# buttons_audio_amplifier.net
KiCad netlist of a schematic drawn in Altium Designer
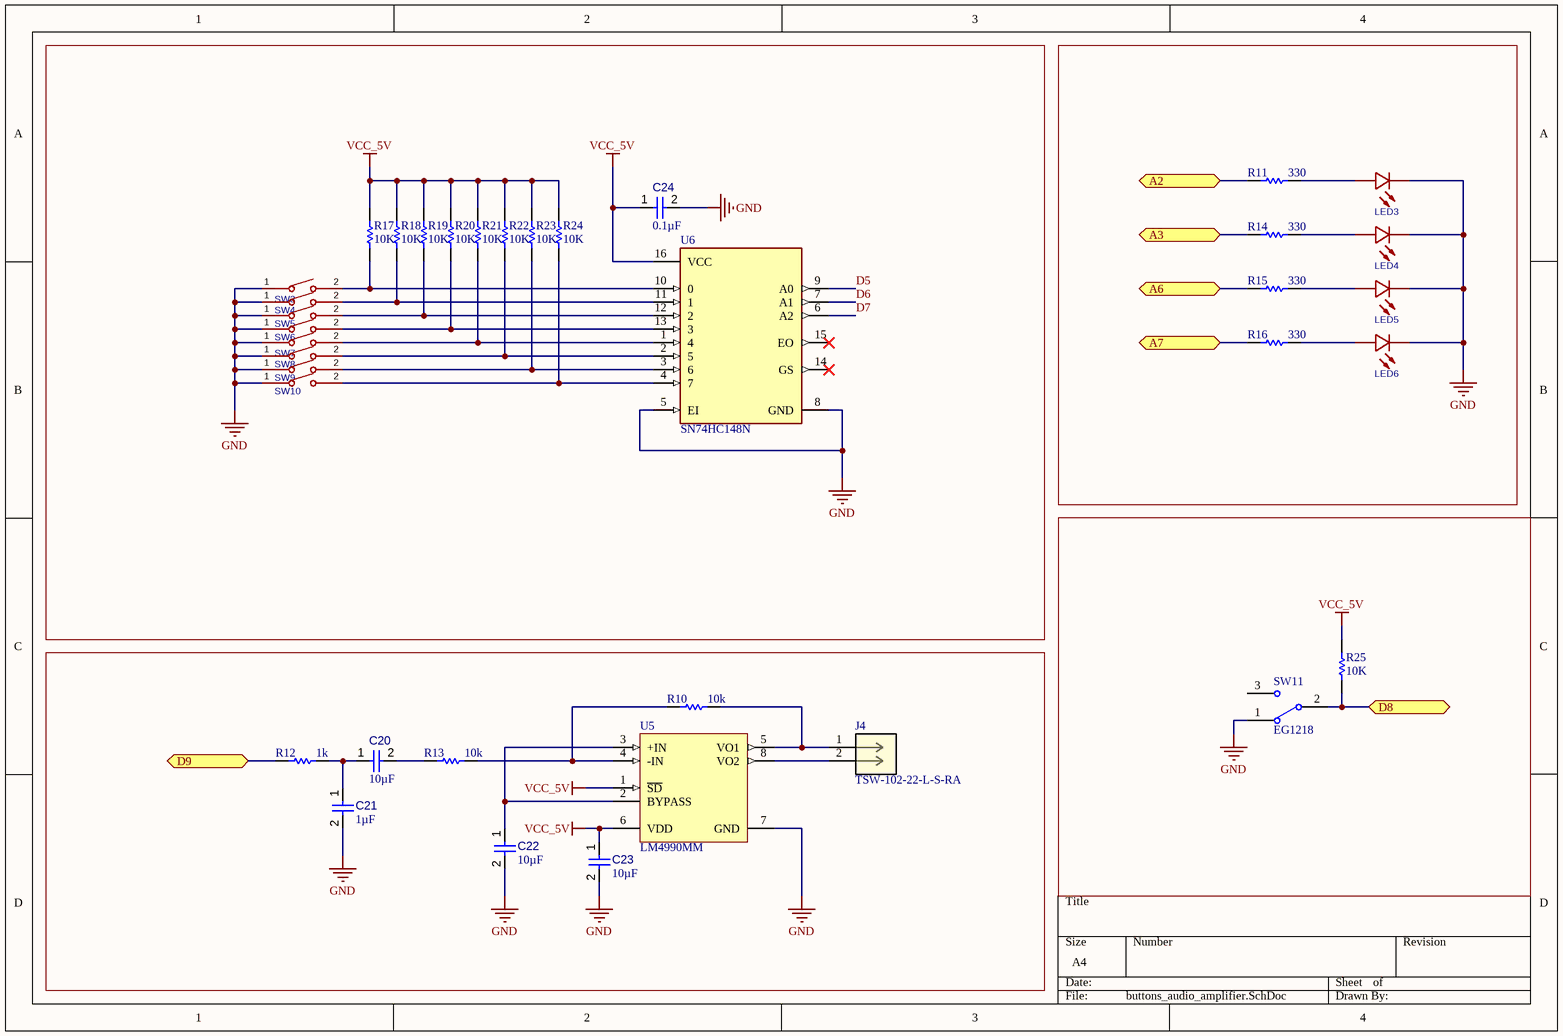
[diagram p0: buttons_audio_amplifier.SchDoc]

(export (version "E")
  (design (tool "Eeschema 10.0.6"))
  (components
    (comp (ref "C20")
      (value "10µF")
      (footprint "CAPC2013X135X45NL10T25")
      (description "Chip Capacitor, 10 uF, +/- 10%, 16 V, 0805 (2012 Metric)")
      (fields (field (name "TOLERANCE") "10%") (field (name "Comment") "Capacitor 10 uF +/- 10% 16 V 0805"))
      (libsource (lib "新宇 付") (part "CAP-NP-2"))
    )
    (comp (ref "C21")
      (value "1µF")
      (footprint "CAPC2013X135X45NL10T25")
      (description "Chip Capacitor, 10 uF, +/- 10%, 16 V, 0805 (2012 Metric)")
      (fields (field (name "TOLERANCE") "10%") (field (name "Comment") "Capacitor 10 uF +/- 10% 16 V 0805"))
      (libsource (lib "新宇 付") (part "CAP-NP-2"))
    )
    (comp (ref "C22")
      (value "10µF")
      (footprint "CAPC2013X135X45NL10T25")
      (description "Chip Capacitor, 10 uF, +/- 10%, 16 V, 0805 (2012 Metric)")
      (fields (field (name "TOLERANCE") "10%") (field (name "Comment") "Capacitor 10 uF +/- 10% 16 V 0805"))
      (libsource (lib "新宇 付") (part "CAP-NP-2"))
    )
    (comp (ref "C23")
      (value "10µF")
      (footprint "CAPC2013X135X45NL10T25")
      (description "Chip Capacitor, 10 uF, +/- 10%, 16 V, 0805 (2012 Metric)")
      (fields (field (name "TOLERANCE") "10%") (field (name "Comment") "Capacitor 10 uF +/- 10% 16 V 0805"))
      (libsource (lib "新宇 付") (part "CAP-NP-2"))
    )
    (comp (ref "C24")
      (value "0.1µF")
      (footprint "CAPC2013X135X45NL10T25")
      (description "Chip Capacitor, 10 uF, +/- 10%, 16 V, 0805 (2012 Metric)")
      (fields (field (name "TOLERANCE") "10%") (field (name "Comment") "Capacitor 10 uF +/- 10% 16 V 0805"))
      (libsource (lib "新宇 付") (part "CAP-NP-2"))
    )
    (comp (ref "J4")
      (value "TSW-102-22-L-S-RA")
      (footprint "CON2_1X2_TR_TSW_SAI")
      (description "No Description Available")
      (fields (field (name "COPYRIGHT") "Copyright (C) 2026 Ultra Librarian. All rights reserved."))
      (libsource (lib "TSW-102-22-L-S-RA") (part "TSW-102-22-L-S-RA"))
    )
    (comp (ref "LED3")
      (value "FC-DA1608HRK-620D")
      (footprint "LED0603-RD_RED")
      (libsource (lib "C84263_发光二极管-LED_0603") (part "FC-DA1608HRK-620D"))
    )
    (comp (ref "LED4")
      (value "FC-DA1608HRK-620D")
      (footprint "LED0603-RD_RED")
      (libsource (lib "C84263_发光二极管-LED_0603") (part "FC-DA1608HRK-620D"))
    )
    (comp (ref "LED5")
      (value "FC-DA1608HRK-620D")
      (footprint "LED0603-RD_RED")
      (libsource (lib "C84263_发光二极管-LED_0603") (part "FC-DA1608HRK-620D"))
    )
    (comp (ref "LED6")
      (value "FC-DA1608HRK-620D")
      (footprint "LED0603-RD_RED")
      (libsource (lib "C84263_发光二极管-LED_0603") (part "FC-DA1608HRK-620D"))
    )
    (comp (ref "R10")
      (value "10k")
      (footprint "RESC2013X50X35ML15T15")
      (description "Chip Resistor, 0 Ohm, +/- 1%, 125 mW, -55 to 155 degC, 0805 (2012 Metric)")
      (fields (field (name "TOLERANCE") "1%") (field (name "POWER") "125mW"))
      (libsource (lib "新宇 付") (part "RES-2"))
    )
    (comp (ref "R11")
      (value "330")
      (footprint "RESC2013X50X35ML15T15")
      (description "Chip Resistor, 0 Ohm, +/- 1%, 125 mW, -55 to 155 degC, 0805 (2012 Metric)")
      (fields (field (name "TOLERANCE") "1%") (field (name "POWER") "125mW"))
      (libsource (lib "新宇 付") (part "RES-2"))
    )
    (comp (ref "R12")
      (value "1k")
      (footprint "RESC2013X50X35ML15T15")
      (description "Chip Resistor, 0 Ohm, +/- 1%, 125 mW, -55 to 155 degC, 0805 (2012 Metric)")
      (fields (field (name "TOLERANCE") "1%") (field (name "POWER") "125mW"))
      (libsource (lib "新宇 付") (part "RES-2"))
    )
    (comp (ref "R13")
      (value "10k")
      (footprint "RESC2013X50X35ML15T15")
      (description "Chip Resistor, 0 Ohm, +/- 1%, 125 mW, -55 to 155 degC, 0805 (2012 Metric)")
      (fields (field (name "TOLERANCE") "1%") (field (name "POWER") "125mW"))
      (libsource (lib "新宇 付") (part "RES-2"))
    )
    (comp (ref "R14")
      (value "330")
      (footprint "RESC2013X50X35ML15T15")
      (description "Chip Resistor, 0 Ohm, +/- 1%, 125 mW, -55 to 155 degC, 0805 (2012 Metric)")
      (fields (field (name "TOLERANCE") "1%") (field (name "POWER") "125mW"))
      (libsource (lib "新宇 付") (part "RES-2"))
    )
    (comp (ref "R15")
      (value "330")
      (footprint "RESC2013X50X35ML15T15")
      (description "Chip Resistor, 0 Ohm, +/- 1%, 125 mW, -55 to 155 degC, 0805 (2012 Metric)")
      (fields (field (name "TOLERANCE") "1%") (field (name "POWER") "125mW"))
      (libsource (lib "新宇 付") (part "RES-2"))
    )
    (comp (ref "R16")
      (value "330")
      (footprint "RESC2013X50X35ML15T15")
      (description "Chip Resistor, 0 Ohm, +/- 1%, 125 mW, -55 to 155 degC, 0805 (2012 Metric)")
      (fields (field (name "TOLERANCE") "1%") (field (name "POWER") "125mW"))
      (libsource (lib "新宇 付") (part "RES-2"))
    )
    (comp (ref "R17")
      (value "10K")
      (footprint "RESC2013X50X35ML15T15")
      (description "Chip Resistor, 0 Ohm, +/- 1%, 125 mW, -55 to 155 degC, 0805 (2012 Metric)")
      (fields (field (name "TOLERANCE") "1%") (field (name "POWER") "125mW"))
      (libsource (lib "新宇 付") (part "RES-2"))
    )
    (comp (ref "R18")
      (value "10K")
      (footprint "RESC2013X50X35ML15T15")
      (description "Chip Resistor, 0 Ohm, +/- 1%, 125 mW, -55 to 155 degC, 0805 (2012 Metric)")
      (fields (field (name "TOLERANCE") "1%") (field (name "POWER") "125mW"))
      (libsource (lib "新宇 付") (part "RES-2"))
    )
    (comp (ref "R19")
      (value "10K")
      (footprint "RESC2013X50X35ML15T15")
      (description "Chip Resistor, 0 Ohm, +/- 1%, 125 mW, -55 to 155 degC, 0805 (2012 Metric)")
      (fields (field (name "TOLERANCE") "1%") (field (name "POWER") "125mW"))
      (libsource (lib "新宇 付") (part "RES-2"))
    )
    (comp (ref "R20")
      (value "10K")
      (footprint "RESC2013X50X35ML15T15")
      (description "Chip Resistor, 0 Ohm, +/- 1%, 125 mW, -55 to 155 degC, 0805 (2012 Metric)")
      (fields (field (name "TOLERANCE") "1%") (field (name "POWER") "125mW"))
      (libsource (lib "新宇 付") (part "RES-2"))
    )
    (comp (ref "R21")
      (value "10K")
      (footprint "RESC2013X50X35ML15T15")
      (description "Chip Resistor, 0 Ohm, +/- 1%, 125 mW, -55 to 155 degC, 0805 (2012 Metric)")
      (fields (field (name "TOLERANCE") "1%") (field (name "POWER") "125mW"))
      (libsource (lib "新宇 付") (part "RES-2"))
    )
    (comp (ref "R22")
      (value "10K")
      (footprint "RESC2013X50X35ML15T15")
      (description "Chip Resistor, 0 Ohm, +/- 1%, 125 mW, -55 to 155 degC, 0805 (2012 Metric)")
      (fields (field (name "TOLERANCE") "1%") (field (name "POWER") "125mW"))
      (libsource (lib "新宇 付") (part "RES-2"))
    )
    (comp (ref "R23")
      (value "10K")
      (footprint "RESC2013X50X35ML15T15")
      (description "Chip Resistor, 0 Ohm, +/- 1%, 125 mW, -55 to 155 degC, 0805 (2012 Metric)")
      (fields (field (name "TOLERANCE") "1%") (field (name "POWER") "125mW"))
      (libsource (lib "新宇 付") (part "RES-2"))
    )
    (comp (ref "R24")
      (value "10K")
      (footprint "RESC2013X50X35ML15T15")
      (description "Chip Resistor, 0 Ohm, +/- 1%, 125 mW, -55 to 155 degC, 0805 (2012 Metric)")
      (fields (field (name "TOLERANCE") "1%") (field (name "POWER") "125mW"))
      (libsource (lib "新宇 付") (part "RES-2"))
    )
    (comp (ref "R25")
      (value "10K")
      (footprint "RESC2013X50X35ML15T15")
      (description "Chip Resistor, 0 Ohm, +/- 1%, 125 mW, -55 to 155 degC, 0805 (2012 Metric)")
      (fields (field (name "TOLERANCE") "1%") (field (name "POWER") "125mW"))
      (libsource (lib "新宇 付") (part "RES-2"))
    )
    (comp (ref "SW3")
      (value "TS-1088-AR02016")
      (footprint "SW-SMD_L3.9-W3.0-P4.45")
      (libsource (lib "Click_switch") (part "TS-1088-AR02016"))
    )
    (comp (ref "SW4")
      (value "TS-1088-AR02016")
      (footprint "SW-SMD_L3.9-W3.0-P4.45")
      (libsource (lib "Click_switch") (part "TS-1088-AR02016"))
    )
    (comp (ref "SW5")
      (value "TS-1088-AR02016")
      (footprint "SW-SMD_L3.9-W3.0-P4.45")
      (libsource (lib "Click_switch") (part "TS-1088-AR02016"))
    )
    (comp (ref "SW6")
      (value "TS-1088-AR02016")
      (footprint "SW-SMD_L3.9-W3.0-P4.45")
      (libsource (lib "Click_switch") (part "TS-1088-AR02016"))
    )
    (comp (ref "SW7")
      (value "TS-1088-AR02016")
      (footprint "SW-SMD_L3.9-W3.0-P4.45")
      (libsource (lib "Click_switch") (part "TS-1088-AR02016"))
    )
    (comp (ref "SW8")
      (value "TS-1088-AR02016")
      (footprint "SW-SMD_L3.9-W3.0-P4.45")
      (libsource (lib "Click_switch") (part "TS-1088-AR02016"))
    )
    (comp (ref "SW9")
      (value "TS-1088-AR02016")
      (footprint "SW-SMD_L3.9-W3.0-P4.45")
      (libsource (lib "Click_switch") (part "TS-1088-AR02016"))
    )
    (comp (ref "SW10")
      (value "TS-1088-AR02016")
      (footprint "SW-SMD_L3.9-W3.0-P4.45")
      (libsource (lib "Click_switch") (part "TS-1088-AR02016"))
    )
    (comp (ref "SW11")
      (value "EG1218")
      (footprint "ESWI-EG1218_V")
      (description "Slide Switch, 500 V, -20 to 70 degC, 3-Pin THD, RoHS")
      (libsource (lib "EG1218单刀双掷滑动开关") (part "CMP-1696-00002-1"))
    )
    (comp (ref "U5")
      (value "LM4990MM")
      (footprint "DGK0008A_N")
      (description "2W Audio Power Amplifier with Selectable Shutdown Logic Level, 8-pin Mini SOIC")
      (fields (field (name "MANUFACTURER") "Texas Instruments"))
      (libsource (lib "Altium Content Vault") (part "AMP-APA-LM4876-8"))
    )
    (comp (ref "U6")
      (value "SN74HC148N")
      (footprint "FP-N0016A-MFG")
      (description "IC PRIORITY ENCOD 1 X 8:3 16DIP")
      (libsource (lib "Altium Content Vault") (part "d5208e0a127fb6c4f39bc57aee2ba58"))
    )
  )
  (nets
    (net (code "1") (name "/A2") (class "Default")
      (node (ref "R11") (pin "1") (pinfunction "1_1") (pintype "passive"))
    )
    (net (code "2") (name "/A3") (class "Default")
      (node (ref "R14") (pin "1") (pinfunction "1_1") (pintype "passive"))
    )
    (net (code "3") (name "/A6") (class "Default")
      (node (ref "R15") (pin "1") (pinfunction "1_1") (pintype "passive"))
    )
    (net (code "4") (name "/A7") (class "Default")
      (node (ref "R16") (pin "1") (pinfunction "1_1") (pintype "passive"))
    )
    (net (code "5") (name "/D5") (class "Default")
      (node (ref "U6") (pin "9") (pinfunction "A0_9") (pintype "output"))
    )
    (net (code "6") (name "/D6") (class "Default")
      (node (ref "U6") (pin "7") (pinfunction "A1_7") (pintype "output"))
    )
    (net (code "7") (name "/D7") (class "Default")
      (node (ref "U6") (pin "6") (pinfunction "A2_6") (pintype "output"))
    )
    (net (code "8") (name "/D8") (class "Default")
      (node (ref "R25") (pin "2") (pinfunction "2_2") (pintype "passive"))
      (node (ref "SW11") (pin "2") (pinfunction "COM_2") (pintype "passive"))
    )
    (net (code "9") (name "/D9") (class "Default")
      (node (ref "R12") (pin "1") (pinfunction "1_1") (pintype "passive"))
    )
    (net (code "10") (name "GND") (class "Default")
      (node (ref "C21") (pin "2") (pinfunction "2_2") (pintype "passive"))
      (node (ref "C22") (pin "2") (pinfunction "2_2") (pintype "passive"))
      (node (ref "C23") (pin "2") (pinfunction "2_2") (pintype "passive"))
      (node (ref "C24") (pin "2") (pinfunction "2_2") (pintype "passive"))
      (node (ref "LED3") (pin "1") (pinfunction "K_1") (pintype "passive"))
      (node (ref "LED4") (pin "1") (pinfunction "K_1") (pintype "passive"))
      (node (ref "LED5") (pin "1") (pinfunction "K_1") (pintype "passive"))
      (node (ref "LED6") (pin "1") (pinfunction "K_1") (pintype "passive"))
      (node (ref "SW10") (pin "1") (pinfunction "1_1") (pintype "passive"))
      (node (ref "SW11") (pin "1") (pinfunction "1_1") (pintype "passive"))
      (node (ref "SW3") (pin "1") (pinfunction "1_1") (pintype "passive"))
      (node (ref "SW4") (pin "1") (pinfunction "1_1") (pintype "passive"))
      (node (ref "SW5") (pin "1") (pinfunction "1_1") (pintype "passive"))
      (node (ref "SW6") (pin "1") (pinfunction "1_1") (pintype "passive"))
      (node (ref "SW7") (pin "1") (pinfunction "1_1") (pintype "passive"))
      (node (ref "SW8") (pin "1") (pinfunction "1_1") (pintype "passive"))
      (node (ref "SW9") (pin "1") (pinfunction "1_1") (pintype "passive"))
      (node (ref "U5") (pin "7") (pinfunction "GND_7") (pintype "power_in"))
      (node (ref "U6") (pin "5") (pinfunction "EI_5") (pintype "input"))
      (node (ref "U6") (pin "8") (pinfunction "GND_8") (pintype "power_in"))
    )
    (net (code "11") (name "Net-(C20-Pad1)") (class "Default")
      (node (ref "C20") (pin "1") (pinfunction "1_1") (pintype "passive"))
      (node (ref "C21") (pin "1") (pinfunction "1_1") (pintype "passive"))
      (node (ref "R12") (pin "2") (pinfunction "2_2") (pintype "passive"))
    )
    (net (code "12") (name "Net-(C20-Pad2)") (class "Default")
      (node (ref "C20") (pin "2") (pinfunction "2_2") (pintype "passive"))
      (node (ref "R13") (pin "1") (pinfunction "1_1") (pintype "passive"))
    )
    (net (code "13") (name "Net-(LED3-A)") (class "Default")
      (node (ref "LED3") (pin "2") (pinfunction "A_2") (pintype "passive"))
      (node (ref "R11") (pin "2") (pinfunction "2_2") (pintype "passive"))
    )
    (net (code "14") (name "Net-(LED4-A)") (class "Default")
      (node (ref "LED4") (pin "2") (pinfunction "A_2") (pintype "passive"))
      (node (ref "R14") (pin "2") (pinfunction "2_2") (pintype "passive"))
    )
    (net (code "15") (name "Net-(LED5-A)") (class "Default")
      (node (ref "LED5") (pin "2") (pinfunction "A_2") (pintype "passive"))
      (node (ref "R15") (pin "2") (pinfunction "2_2") (pintype "passive"))
    )
    (net (code "16") (name "Net-(LED6-A)") (class "Default")
      (node (ref "LED6") (pin "2") (pinfunction "A_2") (pintype "passive"))
      (node (ref "R16") (pin "2") (pinfunction "2_2") (pintype "passive"))
    )
    (net (code "17") (name "Net-(U5-+IN)") (class "Default")
      (node (ref "C22") (pin "1") (pinfunction "1_1") (pintype "passive"))
      (node (ref "U5") (pin "2") (pinfunction "BYPASS_2") (pintype "passive"))
      (node (ref "U5") (pin "3") (pinfunction "+IN_3") (pintype "input"))
    )
    (net (code "18") (name "Net-(U5--IN)") (class "Default")
      (node (ref "R10") (pin "1") (pinfunction "1_1") (pintype "passive"))
      (node (ref "R13") (pin "2") (pinfunction "2_2") (pintype "passive"))
      (node (ref "U5") (pin "4") (pinfunction "-IN_4") (pintype "input"))
    )
    (net (code "19") (name "Net-(U5-VO1)") (class "Default")
      (node (ref "J4") (pin "1") (pinfunction "1_1") (pintype "passive"))
      (node (ref "R10") (pin "2") (pinfunction "2_2") (pintype "passive"))
      (node (ref "U5") (pin "5") (pinfunction "VO1_5") (pintype "output"))
    )
    (net (code "20") (name "Net-(U5-VO2)") (class "Default")
      (node (ref "J4") (pin "2") (pinfunction "2_2") (pintype "passive"))
      (node (ref "U5") (pin "8") (pinfunction "VO2_8") (pintype "output"))
    )
    (net (code "21") (name "Net-(U6-0)") (class "Default")
      (node (ref "R17") (pin "2") (pinfunction "2_2") (pintype "passive"))
      (node (ref "SW3") (pin "2") (pinfunction "2_2") (pintype "passive"))
      (node (ref "U6") (pin "10") (pinfunction "0_10") (pintype "input"))
    )
    (net (code "22") (name "Net-(U6-1)") (class "Default")
      (node (ref "R18") (pin "2") (pinfunction "2_2") (pintype "passive"))
      (node (ref "SW4") (pin "2") (pinfunction "2_2") (pintype "passive"))
      (node (ref "U6") (pin "11") (pinfunction "1_11") (pintype "input"))
    )
    (net (code "23") (name "Net-(U6-2)") (class "Default")
      (node (ref "R19") (pin "2") (pinfunction "2_2") (pintype "passive"))
      (node (ref "SW5") (pin "2") (pinfunction "2_2") (pintype "passive"))
      (node (ref "U6") (pin "12") (pinfunction "2_12") (pintype "input"))
    )
    (net (code "24") (name "Net-(U6-3)") (class "Default")
      (node (ref "R20") (pin "2") (pinfunction "2_2") (pintype "passive"))
      (node (ref "SW6") (pin "2") (pinfunction "2_2") (pintype "passive"))
      (node (ref "U6") (pin "13") (pinfunction "3_13") (pintype "input"))
    )
    (net (code "25") (name "Net-(U6-4)") (class "Default")
      (node (ref "R21") (pin "2") (pinfunction "2_2") (pintype "passive"))
      (node (ref "SW7") (pin "2") (pinfunction "2_2") (pintype "passive"))
      (node (ref "U6") (pin "1") (pinfunction "4_1") (pintype "input"))
    )
    (net (code "26") (name "Net-(U6-5)") (class "Default")
      (node (ref "R22") (pin "2") (pinfunction "2_2") (pintype "passive"))
      (node (ref "SW8") (pin "2") (pinfunction "2_2") (pintype "passive"))
      (node (ref "U6") (pin "2") (pinfunction "5_2") (pintype "input"))
    )
    (net (code "27") (name "Net-(U6-6)") (class "Default")
      (node (ref "R23") (pin "2") (pinfunction "2_2") (pintype "passive"))
      (node (ref "SW9") (pin "2") (pinfunction "2_2") (pintype "passive"))
      (node (ref "U6") (pin "3") (pinfunction "6_3") (pintype "input"))
    )
    (net (code "28") (name "Net-(U6-7)") (class "Default")
      (node (ref "R24") (pin "2") (pinfunction "2_2") (pintype "passive"))
      (node (ref "SW10") (pin "2") (pinfunction "2_2") (pintype "passive"))
      (node (ref "U6") (pin "4") (pinfunction "7_4") (pintype "input"))
    )
    (net (code "29") (name "VCC_5V") (class "Default")
      (node (ref "C23") (pin "1") (pinfunction "1_1") (pintype "passive"))
      (node (ref "C24") (pin "1") (pinfunction "1_1") (pintype "passive"))
      (node (ref "R17") (pin "1") (pinfunction "1_1") (pintype "passive"))
      (node (ref "R18") (pin "1") (pinfunction "1_1") (pintype "passive"))
      (node (ref "R19") (pin "1") (pinfunction "1_1") (pintype "passive"))
      (node (ref "R20") (pin "1") (pinfunction "1_1") (pintype "passive"))
      (node (ref "R21") (pin "1") (pinfunction "1_1") (pintype "passive"))
      (node (ref "R22") (pin "1") (pinfunction "1_1") (pintype "passive"))
      (node (ref "R23") (pin "1") (pinfunction "1_1") (pintype "passive"))
      (node (ref "R24") (pin "1") (pinfunction "1_1") (pintype "passive"))
      (node (ref "R25") (pin "1") (pinfunction "1_1") (pintype "passive"))
      (node (ref "U5") (pin "1") (pinfunction "~{SD}_1") (pintype "input"))
      (node (ref "U5") (pin "6") (pinfunction "VDD_6") (pintype "power_in"))
      (node (ref "U6") (pin "16") (pinfunction "VCC_16") (pintype "power_in"))
    )
    (net (code "30") (name "unconnected-(SW11-Pad3)") (class "Default")
      (node (ref "SW11") (pin "3") (pinfunction "3_3") (pintype "passive"))
    )
    (net (code "31") (name "unconnected-(U6-EO-Pad15)") (class "Default")
      (node (ref "U6") (pin "15") (pinfunction "EO_15") (pintype "output+no_connect"))
    )
    (net (code "32") (name "unconnected-(U6-GS-Pad14)") (class "Default")
      (node (ref "U6") (pin "14") (pinfunction "GS_14") (pintype "output+no_connect"))
    )
  )
)
